# od855_redraw.net
KiCad netlist of a schematic drawn in EAGLE
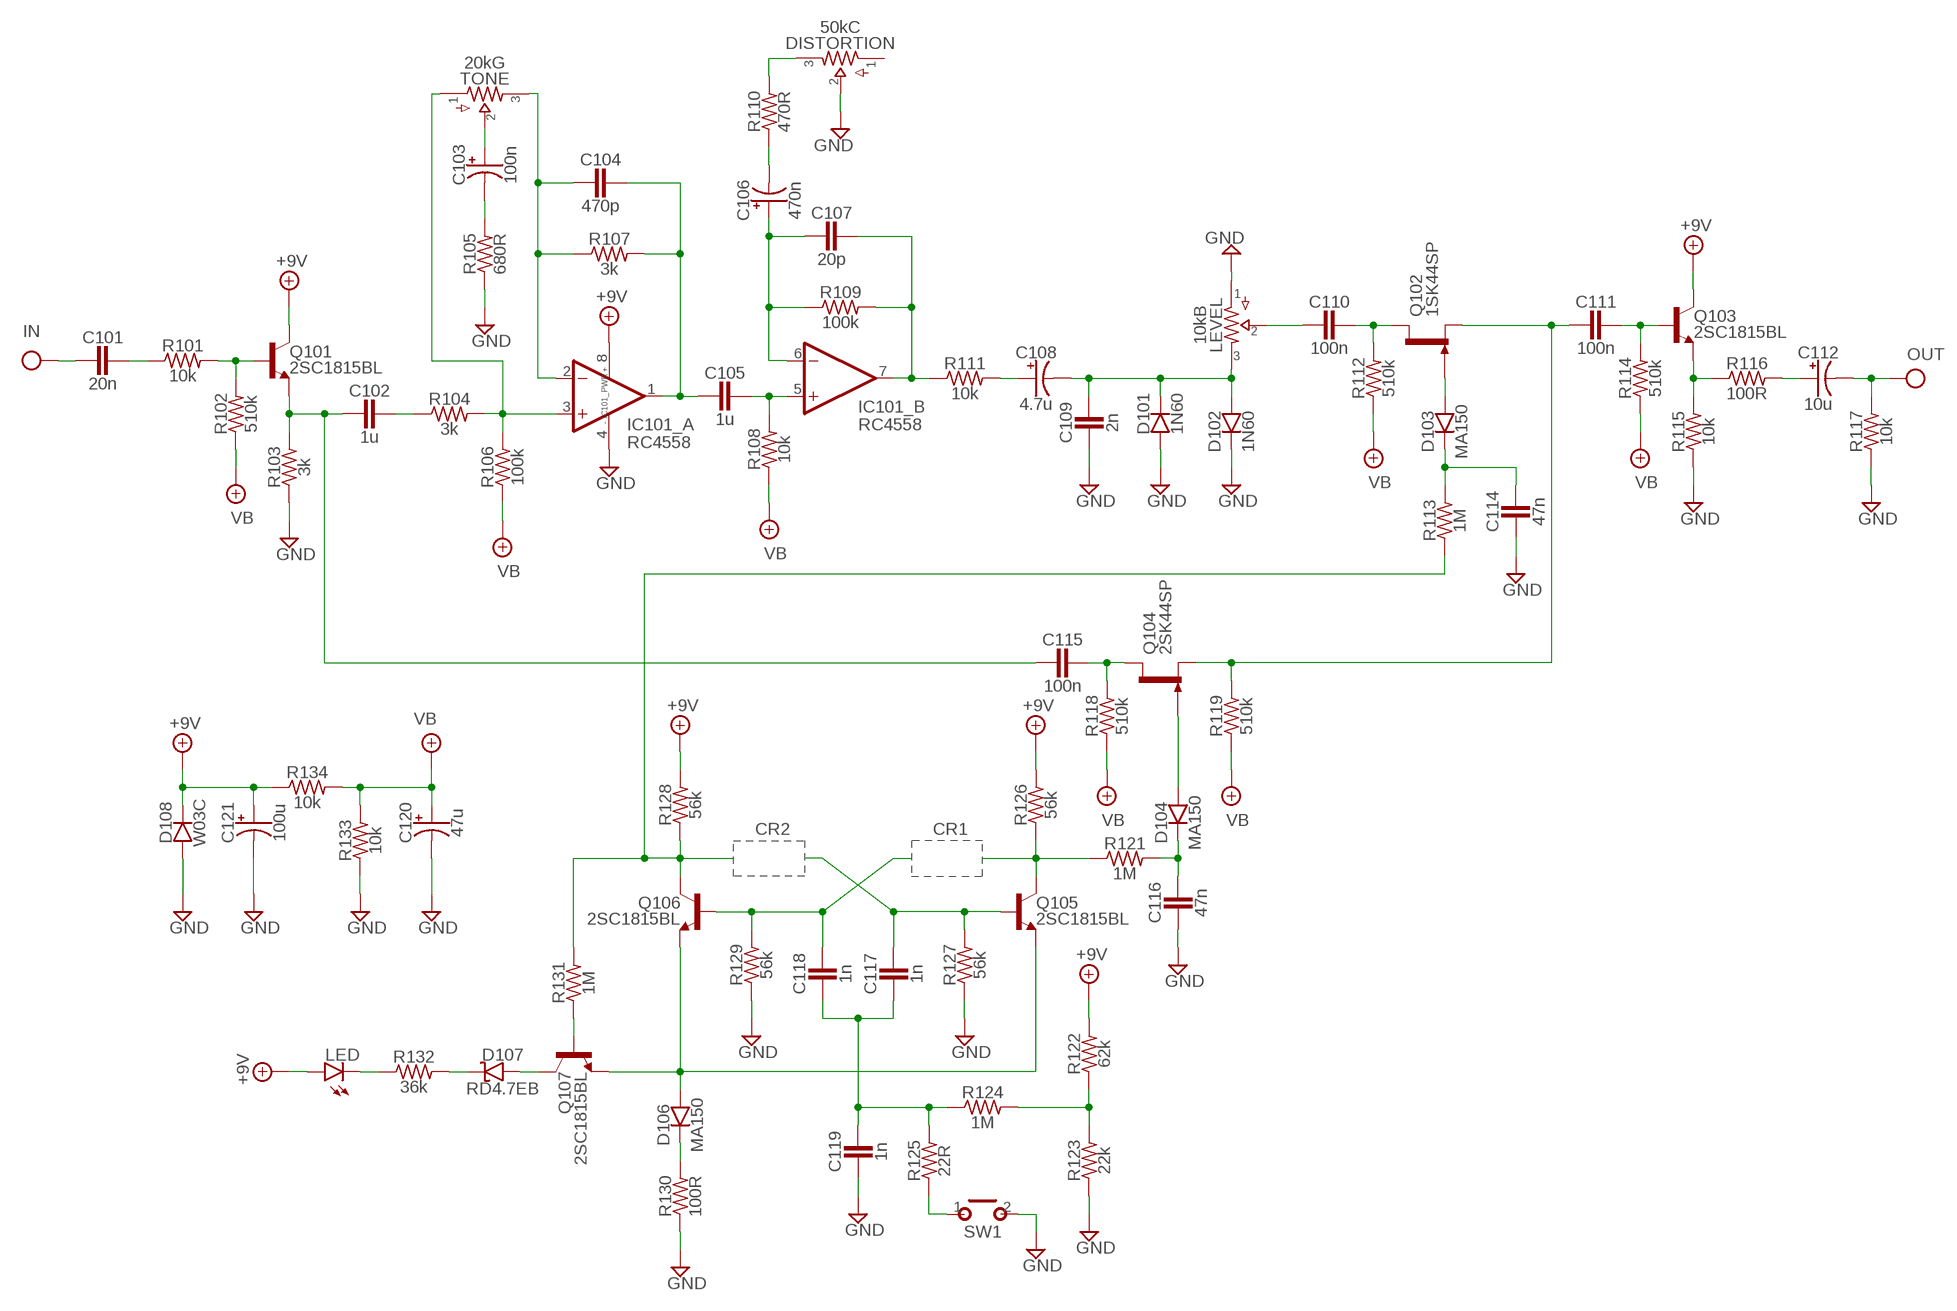
[diagram p0: schematic, sheet 1]

(export (version "E")
  (design (tool "Eeschema 10.0.6"))
  (components
    (comp (ref "C101")
      (value "20n")
      (footprint "eagle-import:BOX_SMALL")
      (libsource (lib "eagle-import") (part "CER/FILMBOX.1"))
    )
    (comp (ref "C102")
      (value "1u")
      (footprint "eagle-import:BOX_SMALL")
      (libsource (lib "eagle-import") (part "CER/FILMBOX.1"))
    )
    (comp (ref "C103")
      (value "100n")
      (footprint "eagle-import:050_020")
      (libsource (lib "eagle-import") (part "0500"))
    )
    (comp (ref "C104")
      (value "470p")
      (footprint "eagle-import:BOX_SMALL")
      (libsource (lib "eagle-import") (part "CER/FILMBOX.1"))
    )
    (comp (ref "C105")
      (value "1u")
      (footprint "eagle-import:BOX_SMALL")
      (libsource (lib "eagle-import") (part "CER/FILMBOX.1"))
    )
    (comp (ref "C106")
      (value "470n")
      (footprint "eagle-import:050_020")
      (libsource (lib "eagle-import") (part "0500"))
    )
    (comp (ref "C107")
      (value "20p")
      (footprint "eagle-import:BOX_SMALL")
      (libsource (lib "eagle-import") (part "CER/FILMBOX.1"))
    )
    (comp (ref "C108")
      (value "4.7u")
      (footprint "eagle-import:050_020")
      (libsource (lib "eagle-import") (part "0500"))
    )
    (comp (ref "C109")
      (value "2n")
      (footprint "eagle-import:BOX_SMALL")
      (libsource (lib "eagle-import") (part "CER/FILMBOX.1"))
    )
    (comp (ref "C110")
      (value "100n")
      (footprint "eagle-import:BOX_SMALL")
      (libsource (lib "eagle-import") (part "CER/FILMBOX.1"))
    )
    (comp (ref "C111")
      (value "100n")
      (footprint "eagle-import:BOX_SMALL")
      (libsource (lib "eagle-import") (part "CER/FILMBOX.1"))
    )
    (comp (ref "C112")
      (value "10u")
      (footprint "eagle-import:050_020")
      (libsource (lib "eagle-import") (part "0500"))
    )
    (comp (ref "C114")
      (value "47n")
      (footprint "eagle-import:BOX_SMALL")
      (libsource (lib "eagle-import") (part "CER/FILMBOX.1"))
    )
    (comp (ref "C115")
      (value "100n")
      (footprint "eagle-import:BOX_SMALL")
      (libsource (lib "eagle-import") (part "CER/FILMBOX.1"))
    )
    (comp (ref "C116")
      (value "47n")
      (footprint "eagle-import:BOX_SMALL")
      (libsource (lib "eagle-import") (part "CER/FILMBOX.1"))
    )
    (comp (ref "C117")
      (value "1n")
      (footprint "eagle-import:BOX_SMALL")
      (libsource (lib "eagle-import") (part "CER/FILMBOX.1"))
    )
    (comp (ref "C118")
      (value "1n")
      (footprint "eagle-import:BOX_SMALL")
      (libsource (lib "eagle-import") (part "CER/FILMBOX.1"))
    )
    (comp (ref "C119")
      (value "1n")
      (footprint "eagle-import:BOX_SMALL")
      (libsource (lib "eagle-import") (part "CER/FILMBOX.1"))
    )
    (comp (ref "C120")
      (value "47u")
      (footprint "eagle-import:050_020")
      (libsource (lib "eagle-import") (part "0500"))
    )
    (comp (ref "C121")
      (value "100u")
      (footprint "eagle-import:050_020")
      (libsource (lib "eagle-import") (part "0500"))
    )
    (comp (ref "D101")
      (value "1N60")
      (footprint "eagle-import:DO35-2")
      (libsource (lib "eagle-import") (part "DO35.2"))
    )
    (comp (ref "D102")
      (value "1N60")
      (footprint "eagle-import:DO35-2")
      (libsource (lib "eagle-import") (part "DO35.2"))
    )
    (comp (ref "D103")
      (value "MA150")
      (footprint "eagle-import:DO35-2")
      (libsource (lib "eagle-import") (part "DO35.2"))
    )
    (comp (ref "D104")
      (value "MA150")
      (footprint "eagle-import:DO35-2")
      (libsource (lib "eagle-import") (part "DO35.2"))
    )
    (comp (ref "D106")
      (value "MA150")
      (footprint "eagle-import:DO35-2")
      (libsource (lib "eagle-import") (part "DO35.2"))
    )
    (comp (ref "D107")
      (value "RD4.7EB")
      (footprint "eagle-import:DO41-2")
      (libsource (lib "eagle-import") (part "ZENER.2"))
    )
    (comp (ref "D108")
      (value "W03C")
      (footprint "eagle-import:DO35-2")
      (libsource (lib "eagle-import") (part "DO35.2"))
    )
    (comp (ref "DISTORTION")
      (value "50kC")
      (footprint "eagle-import:16MM")
      (libsource (lib "eagle-import") (part "POTS16MM"))
    )
    (comp (ref "IC101")
      (value "RC4558")
      (footprint "eagle-import:DIL0")
      (libsource (lib "eagle-import") (part "DUALTH"))
    )
    (comp (ref "LED")
      (value "LED")
      (footprint "eagle-import:3MM_D")
      (libsource (lib "eagle-import") (part "LED"))
    )
    (comp (ref "LEVEL")
      (value "10kB")
      (footprint "eagle-import:16MM")
      (libsource (lib "eagle-import") (part "POTS16MM"))
    )
    (comp (ref "Q101")
      (value "2SC1815BL")
      (footprint "eagle-import:TO92-")
      (libsource (lib "eagle-import") (part "2N3904"))
    )
    (comp (ref "Q102")
      (value "1SK44SP")
      (footprint "eagle-import:TO92-")
      (libsource (lib "eagle-import") (part "2N5457"))
    )
    (comp (ref "Q103")
      (value "2SC1815BL")
      (footprint "eagle-import:TO92-")
      (libsource (lib "eagle-import") (part "2N3904"))
    )
    (comp (ref "Q104")
      (value "2SK44SP")
      (footprint "eagle-import:TO92-")
      (libsource (lib "eagle-import") (part "2N5457"))
    )
    (comp (ref "Q105")
      (value "2SC1815BL")
      (footprint "eagle-import:TO92-")
      (libsource (lib "eagle-import") (part "2SC828A"))
    )
    (comp (ref "Q106")
      (value "2SC1815BL")
      (footprint "eagle-import:TO92-")
      (libsource (lib "eagle-import") (part "2SC828A"))
    )
    (comp (ref "Q107")
      (value "2SC1815BL")
      (footprint "eagle-import:TO92-")
      (libsource (lib "eagle-import") (part "2SC828A"))
    )
    (comp (ref "R101")
      (value "10k")
      (footprint "eagle-import:R0207_3")
      (libsource (lib "eagle-import") (part "R_.3B"))
    )
    (comp (ref "R102")
      (value "510k")
      (footprint "eagle-import:R0207_3")
      (libsource (lib "eagle-import") (part "R_.3B"))
    )
    (comp (ref "R103")
      (value "3k")
      (footprint "eagle-import:R0207_3")
      (libsource (lib "eagle-import") (part "R_.3B"))
    )
    (comp (ref "R104")
      (value "3k")
      (footprint "eagle-import:R0207_3")
      (libsource (lib "eagle-import") (part "R_.3B"))
    )
    (comp (ref "R105")
      (value "680R")
      (footprint "eagle-import:R0207_3")
      (libsource (lib "eagle-import") (part "R_.3B"))
    )
    (comp (ref "R106")
      (value "100k")
      (footprint "eagle-import:R0207_3")
      (libsource (lib "eagle-import") (part "R_.3B"))
    )
    (comp (ref "R107")
      (value "3k")
      (footprint "eagle-import:R0207_3")
      (libsource (lib "eagle-import") (part "R_.3B"))
    )
    (comp (ref "R108")
      (value "10k")
      (footprint "eagle-import:R0207_3")
      (libsource (lib "eagle-import") (part "R_.3B"))
    )
    (comp (ref "R109")
      (value "100k")
      (footprint "eagle-import:R0207_3")
      (libsource (lib "eagle-import") (part "R_.3B"))
    )
    (comp (ref "R110")
      (value "470R")
      (footprint "eagle-import:R0207_3")
      (libsource (lib "eagle-import") (part "R_.3B"))
    )
    (comp (ref "R111")
      (value "10k")
      (footprint "eagle-import:R0207_3")
      (libsource (lib "eagle-import") (part "R_.3B"))
    )
    (comp (ref "R112")
      (value "510k")
      (footprint "eagle-import:R0207_3")
      (libsource (lib "eagle-import") (part "R_.3B"))
    )
    (comp (ref "R113")
      (value "1M")
      (footprint "eagle-import:R0207_3")
      (libsource (lib "eagle-import") (part "R_.3B"))
    )
    (comp (ref "R114")
      (value "510k")
      (footprint "eagle-import:R0207_3")
      (libsource (lib "eagle-import") (part "R_.3B"))
    )
    (comp (ref "R115")
      (value "10k")
      (footprint "eagle-import:R0207_3")
      (libsource (lib "eagle-import") (part "R_.3B"))
    )
    (comp (ref "R116")
      (value "100R")
      (footprint "eagle-import:R0207_3")
      (libsource (lib "eagle-import") (part "R_.3B"))
    )
    (comp (ref "R117")
      (value "10k")
      (footprint "eagle-import:R0207_3")
      (libsource (lib "eagle-import") (part "R_.3B"))
    )
    (comp (ref "R118")
      (value "510k")
      (footprint "eagle-import:R0207_3")
      (libsource (lib "eagle-import") (part "R_.3B"))
    )
    (comp (ref "R119")
      (value "510k")
      (footprint "eagle-import:R0207_3")
      (libsource (lib "eagle-import") (part "R_.3B"))
    )
    (comp (ref "R121")
      (value "1M")
      (footprint "eagle-import:R0207_3")
      (libsource (lib "eagle-import") (part "R_.3B"))
    )
    (comp (ref "R122")
      (value "62k")
      (footprint "eagle-import:R0207_3")
      (libsource (lib "eagle-import") (part "R_.3B"))
    )
    (comp (ref "R123")
      (value "22k")
      (footprint "eagle-import:R0207_3")
      (libsource (lib "eagle-import") (part "R_.3B"))
    )
    (comp (ref "R124")
      (value "1M")
      (footprint "eagle-import:R0207_3")
      (libsource (lib "eagle-import") (part "R_.3B"))
    )
    (comp (ref "R125")
      (value "22R")
      (footprint "eagle-import:R0207_3")
      (libsource (lib "eagle-import") (part "R_.3B"))
    )
    (comp (ref "R126")
      (value "56k")
      (footprint "eagle-import:R0207_3")
      (libsource (lib "eagle-import") (part "R_.3B"))
    )
    (comp (ref "R127")
      (value "56k")
      (footprint "eagle-import:R0207_3")
      (libsource (lib "eagle-import") (part "R_.3B"))
    )
    (comp (ref "R128")
      (value "56k")
      (footprint "eagle-import:R0207_3")
      (libsource (lib "eagle-import") (part "R_.3B"))
    )
    (comp (ref "R129")
      (value "56k")
      (footprint "eagle-import:R0207_3")
      (libsource (lib "eagle-import") (part "R_.3B"))
    )
    (comp (ref "R130")
      (value "100R")
      (footprint "eagle-import:R0207_3")
      (libsource (lib "eagle-import") (part "R_.3B"))
    )
    (comp (ref "R131")
      (value "1M")
      (footprint "eagle-import:R0207_3")
      (libsource (lib "eagle-import") (part "R_.3B"))
    )
    (comp (ref "R132")
      (value "36k")
      (footprint "eagle-import:R0207_3")
      (libsource (lib "eagle-import") (part "R_.3B"))
    )
    (comp (ref "R133")
      (value "10k")
      (footprint "eagle-import:R0207_3")
      (libsource (lib "eagle-import") (part "R_.3B"))
    )
    (comp (ref "R134")
      (value "10k")
      (footprint "eagle-import:R0207_3")
      (libsource (lib "eagle-import") (part "R_.3B"))
    )
    (comp (ref "SW1")
      (value "MOMENTARY")
      (footprint "eagle-import:SPST")
      (libsource (lib "eagle-import") (part "MOMENTARY"))
    )
    (comp (ref "TONE")
      (value "20kG")
      (footprint "eagle-import:16MM")
      (libsource (lib "eagle-import") (part "POTS16MM"))
    )
  )
  (nets
    (net (code "1") (name "+9V") (class "Default")
      (node (ref "C121") (pin "+") (pinfunction "+_+") (pintype "passive"))
      (node (ref "D108") (pin "C") (pinfunction "C_C") (pintype "passive"))
      (node (ref "IC101") (pin "8") (pinfunction "V+_8") (pintype "power_in"))
      (node (ref "LED") (pin "ANODE") (pinfunction "A_ANODE") (pintype "passive"))
      (node (ref "Q101") (pin "1") (pinfunction "C_1") (pintype "passive"))
      (node (ref "Q103") (pin "1") (pinfunction "C_1") (pintype "passive"))
      (node (ref "R122") (pin "2") (pinfunction "2_2") (pintype "passive"))
      (node (ref "R126") (pin "2") (pinfunction "2_2") (pintype "passive"))
      (node (ref "R128") (pin "2") (pinfunction "2_2") (pintype "passive"))
      (node (ref "R134") (pin "1") (pinfunction "1_1") (pintype "passive"))
    )
    (net (code "2") (name "GND") (class "Default")
      (node (ref "C109") (pin "2") (pinfunction "2_2") (pintype "passive"))
      (node (ref "C114") (pin "2") (pinfunction "2_2") (pintype "passive"))
      (node (ref "C116") (pin "2") (pinfunction "2_2") (pintype "passive"))
      (node (ref "C119") (pin "2") (pinfunction "2_2") (pintype "passive"))
      (node (ref "C120") (pin "-") (pinfunction "-_-") (pintype "passive"))
      (node (ref "C121") (pin "-") (pinfunction "-_-") (pintype "passive"))
      (node (ref "D101") (pin "A") (pinfunction "A_A") (pintype "passive"))
      (node (ref "D102") (pin "C") (pinfunction "C_C") (pintype "passive"))
      (node (ref "D108") (pin "A") (pinfunction "A_A") (pintype "passive"))
      (node (ref "DISTORTION") (pin "2") (pinfunction "2_2") (pintype "passive"))
      (node (ref "IC101") (pin "4") (pinfunction "V-_4") (pintype "power_in"))
      (node (ref "LEVEL") (pin "1") (pinfunction "1_1") (pintype "passive"))
      (node (ref "R103") (pin "1") (pinfunction "1_1") (pintype "passive"))
      (node (ref "R105") (pin "1") (pinfunction "1_1") (pintype "passive"))
      (node (ref "R115") (pin "1") (pinfunction "1_1") (pintype "passive"))
      (node (ref "R117") (pin "1") (pinfunction "1_1") (pintype "passive"))
      (node (ref "R123") (pin "1") (pinfunction "1_1") (pintype "passive"))
      (node (ref "R127") (pin "1") (pinfunction "1_1") (pintype "passive"))
      (node (ref "R129") (pin "1") (pinfunction "1_1") (pintype "passive"))
      (node (ref "R130") (pin "1") (pinfunction "1_1") (pintype "passive"))
      (node (ref "R133") (pin "1") (pinfunction "1_1") (pintype "passive"))
      (node (ref "SW1") (pin "2") (pinfunction "S_2") (pintype "passive"))
    )
    (net (code "3") (name "IN") (class "Default")
      (node (ref "C101") (pin "2") (pinfunction "2_2") (pintype "passive"))
    )
    (net (code "4") (name "Net-(C101-Pad1)") (class "Default")
      (node (ref "C101") (pin "1") (pinfunction "1_1") (pintype "passive"))
      (node (ref "R101") (pin "1") (pinfunction "1_1") (pintype "passive"))
    )
    (net (code "5") (name "Net-(C102-Pad1)") (class "Default")
      (node (ref "C102") (pin "1") (pinfunction "1_1") (pintype "passive"))
      (node (ref "R104") (pin "1") (pinfunction "1_1") (pintype "passive"))
    )
    (net (code "6") (name "Net-(C103-Pad+)") (class "Default")
      (node (ref "C103") (pin "+") (pinfunction "+_+") (pintype "passive"))
      (node (ref "TONE") (pin "2") (pinfunction "2_2") (pintype "passive"))
    )
    (net (code "7") (name "Net-(C103-Pad-)") (class "Default")
      (node (ref "C103") (pin "-") (pinfunction "-_-") (pintype "passive"))
      (node (ref "R105") (pin "2") (pinfunction "2_2") (pintype "passive"))
    )
    (net (code "8") (name "Net-(C106-Pad-)") (class "Default")
      (node (ref "C106") (pin "-") (pinfunction "-_-") (pintype "passive"))
      (node (ref "R110") (pin "1") (pinfunction "1_1") (pintype "passive"))
    )
    (net (code "9") (name "Net-(C108-Pad+)") (class "Default")
      (node (ref "C108") (pin "+") (pinfunction "+_+") (pintype "passive"))
      (node (ref "R111") (pin "2") (pinfunction "2_2") (pintype "passive"))
    )
    (net (code "10") (name "Net-(C108-Pad-)") (class "Default")
      (node (ref "C108") (pin "-") (pinfunction "-_-") (pintype "passive"))
      (node (ref "C109") (pin "1") (pinfunction "1_1") (pintype "passive"))
      (node (ref "D101") (pin "C") (pinfunction "C_C") (pintype "passive"))
      (node (ref "D102") (pin "A") (pinfunction "A_A") (pintype "passive"))
      (node (ref "LEVEL") (pin "3") (pinfunction "3_3") (pintype "passive"))
    )
    (net (code "11") (name "Net-(C110-Pad2)") (class "Default")
      (node (ref "C110") (pin "2") (pinfunction "2_2") (pintype "passive"))
      (node (ref "LEVEL") (pin "2") (pinfunction "2_2") (pintype "passive"))
    )
    (net (code "12") (name "Net-(C112-Pad+)") (class "Default")
      (node (ref "C112") (pin "+") (pinfunction "+_+") (pintype "passive"))
      (node (ref "R116") (pin "2") (pinfunction "2_2") (pintype "passive"))
    )
    (net (code "13") (name "Net-(C114-Pad1)") (class "Default")
      (node (ref "C114") (pin "1") (pinfunction "1_1") (pintype "passive"))
      (node (ref "D103") (pin "C") (pinfunction "C_C") (pintype "passive"))
      (node (ref "R113") (pin "2") (pinfunction "2_2") (pintype "passive"))
    )
    (net (code "14") (name "Net-(C116-Pad1)") (class "Default")
      (node (ref "C116") (pin "1") (pinfunction "1_1") (pintype "passive"))
      (node (ref "D104") (pin "C") (pinfunction "C_C") (pintype "passive"))
      (node (ref "R121") (pin "2") (pinfunction "2_2") (pintype "passive"))
    )
    (net (code "15") (name "Net-(C117-Pad2)") (class "Default")
      (node (ref "C117") (pin "2") (pinfunction "2_2") (pintype "passive"))
      (node (ref "C118") (pin "2") (pinfunction "2_2") (pintype "passive"))
      (node (ref "C119") (pin "1") (pinfunction "1_1") (pintype "passive"))
      (node (ref "R124") (pin "1") (pinfunction "1_1") (pintype "passive"))
      (node (ref "R125") (pin "2") (pinfunction "2_2") (pintype "passive"))
    )
    (net (code "16") (name "Net-(D106-PadC)") (class "Default")
      (node (ref "D106") (pin "C") (pinfunction "C_C") (pintype "passive"))
      (node (ref "R130") (pin "2") (pinfunction "2_2") (pintype "passive"))
    )
    (net (code "17") (name "Net-(D107-PadC)") (class "Default")
      (node (ref "D107") (pin "C") (pinfunction "C_C") (pintype "passive"))
      (node (ref "R132") (pin "2") (pinfunction "2_2") (pintype "passive"))
    )
    (net (code "18") (name "Net-(DISTORTION-Pad3)") (class "Default")
      (node (ref "DISTORTION") (pin "3") (pinfunction "3_3") (pintype "passive"))
      (node (ref "R110") (pin "2") (pinfunction "2_2") (pintype "passive"))
    )
    (net (code "19") (name "Net-(IC101A-+IN)") (class "Default")
      (node (ref "IC101") (pin "3") (pinfunction "+IN_3") (pintype "input"))
      (node (ref "R104") (pin "2") (pinfunction "2_2") (pintype "passive"))
      (node (ref "R106") (pin "2") (pinfunction "2_2") (pintype "passive"))
      (node (ref "TONE") (pin "1") (pinfunction "1_1") (pintype "passive"))
    )
    (net (code "20") (name "Net-(IC101A--IN)") (class "Default")
      (node (ref "C104") (pin "2") (pinfunction "2_2") (pintype "passive"))
      (node (ref "IC101") (pin "2") (pinfunction "-IN_2") (pintype "input"))
      (node (ref "R107") (pin "1") (pinfunction "1_1") (pintype "passive"))
      (node (ref "TONE") (pin "3") (pinfunction "3_3") (pintype "passive"))
    )
    (net (code "21") (name "Net-(IC101A-OUT)") (class "Default")
      (node (ref "C104") (pin "1") (pinfunction "1_1") (pintype "passive"))
      (node (ref "C105") (pin "2") (pinfunction "2_2") (pintype "passive"))
      (node (ref "IC101") (pin "1") (pinfunction "OUT_1") (pintype "output"))
      (node (ref "R107") (pin "2") (pinfunction "2_2") (pintype "passive"))
    )
    (net (code "22") (name "Net-(IC101B-+IN)") (class "Default")
      (node (ref "C105") (pin "1") (pinfunction "1_1") (pintype "passive"))
      (node (ref "IC101") (pin "5") (pinfunction "+IN_5") (pintype "input"))
      (node (ref "R108") (pin "2") (pinfunction "2_2") (pintype "passive"))
    )
    (net (code "23") (name "Net-(IC101B--IN)") (class "Default")
      (node (ref "C106") (pin "+") (pinfunction "+_+") (pintype "passive"))
      (node (ref "C107") (pin "2") (pinfunction "2_2") (pintype "passive"))
      (node (ref "IC101") (pin "6") (pinfunction "-IN_6") (pintype "input"))
      (node (ref "R109") (pin "1") (pinfunction "1_1") (pintype "passive"))
    )
    (net (code "24") (name "Net-(IC101B-OUT)") (class "Default")
      (node (ref "C107") (pin "1") (pinfunction "1_1") (pintype "passive"))
      (node (ref "IC101") (pin "7") (pinfunction "OUT_7") (pintype "output"))
      (node (ref "R109") (pin "2") (pinfunction "2_2") (pintype "passive"))
      (node (ref "R111") (pin "1") (pinfunction "1_1") (pintype "passive"))
    )
    (net (code "25") (name "Net-(LED-C)") (class "Default")
      (node (ref "LED") (pin "P$1") (pinfunction "C_P$1") (pintype "passive"))
      (node (ref "R132") (pin "1") (pinfunction "1_1") (pintype "passive"))
    )
    (net (code "26") (name "Net-(Q101-B)") (class "Default")
      (node (ref "Q101") (pin "2") (pinfunction "B_2") (pintype "passive"))
      (node (ref "R101") (pin "2") (pinfunction "2_2") (pintype "passive"))
      (node (ref "R102") (pin "2") (pinfunction "2_2") (pintype "passive"))
    )
    (net (code "27") (name "Net-(Q101-E)") (class "Default")
      (node (ref "C102") (pin "2") (pinfunction "2_2") (pintype "passive"))
      (node (ref "C115") (pin "2") (pinfunction "2_2") (pintype "passive"))
      (node (ref "Q101") (pin "3") (pinfunction "E_3") (pintype "passive"))
      (node (ref "R103") (pin "2") (pinfunction "2_2") (pintype "passive"))
    )
    (net (code "28") (name "Net-(Q102-D)") (class "Default")
      (node (ref "C110") (pin "1") (pinfunction "1_1") (pintype "passive"))
      (node (ref "Q102") (pin "3") (pinfunction "D_3") (pintype "passive"))
      (node (ref "R112") (pin "2") (pinfunction "2_2") (pintype "passive"))
    )
    (net (code "29") (name "Net-(Q102-G)") (class "Default")
      (node (ref "D103") (pin "A") (pinfunction "A_A") (pintype "passive"))
      (node (ref "Q102") (pin "1") (pinfunction "G_1") (pintype "passive"))
    )
    (net (code "30") (name "Net-(Q102-S)") (class "Default")
      (node (ref "C111") (pin "2") (pinfunction "2_2") (pintype "passive"))
      (node (ref "Q102") (pin "2") (pinfunction "S_2") (pintype "passive"))
      (node (ref "Q104") (pin "2") (pinfunction "S_2") (pintype "passive"))
      (node (ref "R119") (pin "2") (pinfunction "2_2") (pintype "passive"))
    )
    (net (code "31") (name "Net-(Q103-B)") (class "Default")
      (node (ref "C111") (pin "1") (pinfunction "1_1") (pintype "passive"))
      (node (ref "Q103") (pin "2") (pinfunction "B_2") (pintype "passive"))
      (node (ref "R114") (pin "2") (pinfunction "2_2") (pintype "passive"))
    )
    (net (code "32") (name "Net-(Q103-E)") (class "Default")
      (node (ref "Q103") (pin "3") (pinfunction "E_3") (pintype "passive"))
      (node (ref "R115") (pin "2") (pinfunction "2_2") (pintype "passive"))
      (node (ref "R116") (pin "1") (pinfunction "1_1") (pintype "passive"))
    )
    (net (code "33") (name "Net-(Q104-D)") (class "Default")
      (node (ref "C115") (pin "1") (pinfunction "1_1") (pintype "passive"))
      (node (ref "Q104") (pin "3") (pinfunction "D_3") (pintype "passive"))
      (node (ref "R118") (pin "2") (pinfunction "2_2") (pintype "passive"))
    )
    (net (code "34") (name "Net-(Q104-G)") (class "Default")
      (node (ref "D104") (pin "A") (pinfunction "A_A") (pintype "passive"))
      (node (ref "Q104") (pin "1") (pinfunction "G_1") (pintype "passive"))
    )
    (net (code "35") (name "Net-(Q105-B)") (class "Default")
      (node (ref "C117") (pin "1") (pinfunction "1_1") (pintype "passive"))
      (node (ref "Q105") (pin "1") (pinfunction "B_1") (pintype "passive"))
      (node (ref "R127") (pin "2") (pinfunction "2_2") (pintype "passive"))
    )
    (net (code "36") (name "Net-(Q105-C)") (class "Default")
      (node (ref "Q105") (pin "2") (pinfunction "C_2") (pintype "passive"))
      (node (ref "R121") (pin "1") (pinfunction "1_1") (pintype "passive"))
      (node (ref "R126") (pin "1") (pinfunction "1_1") (pintype "passive"))
    )
    (net (code "37") (name "Net-(Q105-E)") (class "Default")
      (node (ref "D106") (pin "A") (pinfunction "A_A") (pintype "passive"))
      (node (ref "Q105") (pin "3") (pinfunction "E_3") (pintype "passive"))
      (node (ref "Q106") (pin "3") (pinfunction "E_3") (pintype "passive"))
      (node (ref "Q107") (pin "3") (pinfunction "E_3") (pintype "passive"))
    )
    (net (code "38") (name "Net-(Q106-B)") (class "Default")
      (node (ref "C118") (pin "1") (pinfunction "1_1") (pintype "passive"))
      (node (ref "Q106") (pin "1") (pinfunction "B_1") (pintype "passive"))
      (node (ref "R129") (pin "2") (pinfunction "2_2") (pintype "passive"))
    )
    (net (code "39") (name "Net-(Q106-C)") (class "Default")
      (node (ref "Q106") (pin "2") (pinfunction "C_2") (pintype "passive"))
      (node (ref "R113") (pin "1") (pinfunction "1_1") (pintype "passive"))
      (node (ref "R128") (pin "1") (pinfunction "1_1") (pintype "passive"))
      (node (ref "R131") (pin "2") (pinfunction "2_2") (pintype "passive"))
    )
    (net (code "40") (name "Net-(Q107-B)") (class "Default")
      (node (ref "Q107") (pin "1") (pinfunction "B_1") (pintype "passive"))
      (node (ref "R131") (pin "1") (pinfunction "1_1") (pintype "passive"))
    )
    (net (code "41") (name "Net-(Q107-C)") (class "Default")
      (node (ref "D107") (pin "A") (pinfunction "A_A") (pintype "passive"))
      (node (ref "Q107") (pin "2") (pinfunction "C_2") (pintype "passive"))
    )
    (net (code "42") (name "Net-(R122-Pad1)") (class "Default")
      (node (ref "R122") (pin "1") (pinfunction "1_1") (pintype "passive"))
      (node (ref "R123") (pin "2") (pinfunction "2_2") (pintype "passive"))
      (node (ref "R124") (pin "2") (pinfunction "2_2") (pintype "passive"))
    )
    (net (code "43") (name "Net-(SW1-P)") (class "Default")
      (node (ref "R125") (pin "1") (pinfunction "1_1") (pintype "passive"))
      (node (ref "SW1") (pin "1") (pinfunction "P_1") (pintype "passive"))
    )
    (net (code "44") (name "OUT") (class "Default")
      (node (ref "C112") (pin "-") (pinfunction "-_-") (pintype "passive"))
      (node (ref "R117") (pin "2") (pinfunction "2_2") (pintype "passive"))
    )
    (net (code "45") (name "VB") (class "Default")
      (node (ref "C120") (pin "+") (pinfunction "+_+") (pintype "passive"))
      (node (ref "R102") (pin "1") (pinfunction "1_1") (pintype "passive"))
      (node (ref "R106") (pin "1") (pinfunction "1_1") (pintype "passive"))
      (node (ref "R108") (pin "1") (pinfunction "1_1") (pintype "passive"))
      (node (ref "R112") (pin "1") (pinfunction "1_1") (pintype "passive"))
      (node (ref "R114") (pin "1") (pinfunction "1_1") (pintype "passive"))
      (node (ref "R118") (pin "1") (pinfunction "1_1") (pintype "passive"))
      (node (ref "R119") (pin "1") (pinfunction "1_1") (pintype "passive"))
      (node (ref "R133") (pin "2") (pinfunction "2_2") (pintype "passive"))
      (node (ref "R134") (pin "2") (pinfunction "2_2") (pintype "passive"))
    )
    (net (code "46") (name "unconnected-(DISTORTION-Pad1)") (class "Default")
      (node (ref "DISTORTION") (pin "1") (pinfunction "1_1") (pintype "passive"))
    )
  )
)
